# EpaperTeensyBoard.net
KiCad netlist of a schematic drawn in EAGLE
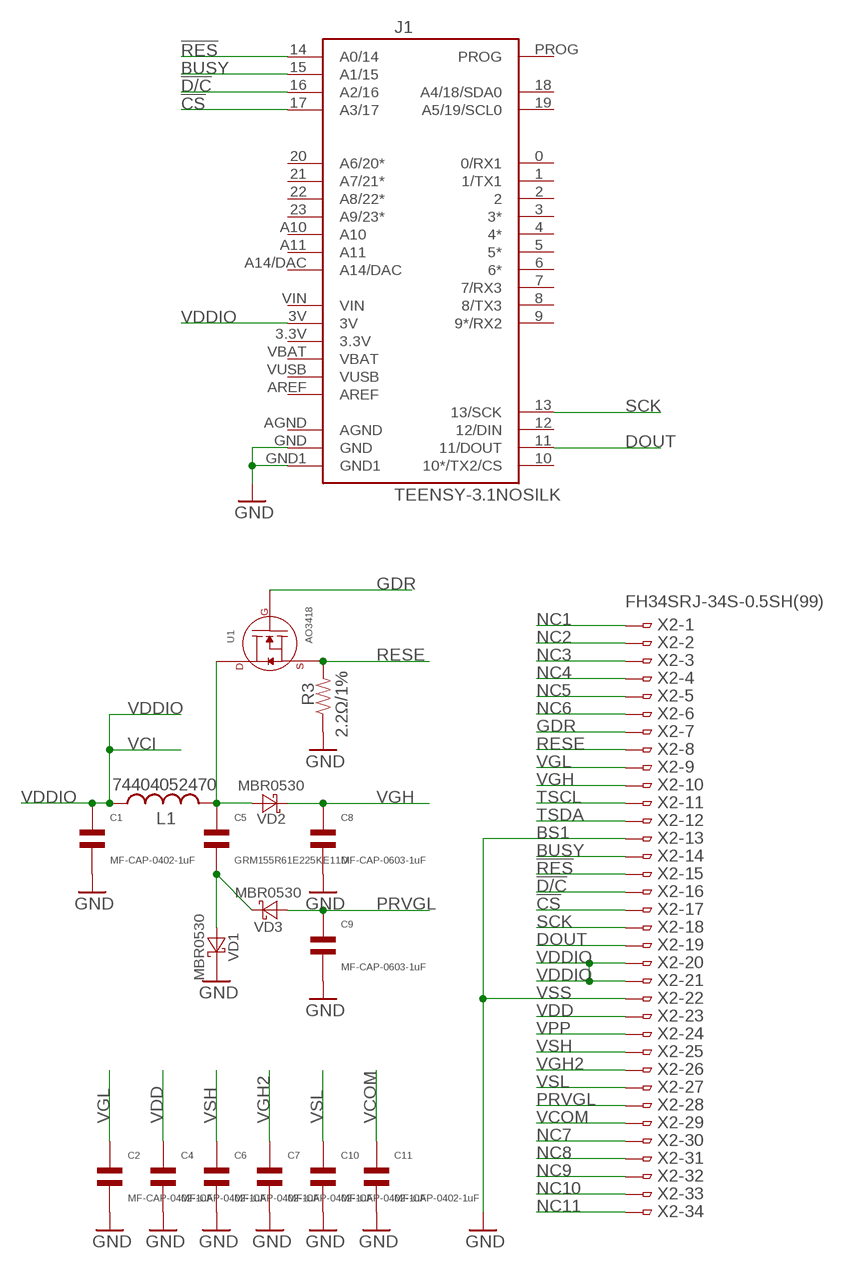
[diagram p0: schematic, sheet 1]

(export (version "E")
  (design (tool "Eeschema 10.0.6"))
  (components
    (comp (ref "C1")
      (value "MF-CAP-0402-1uF")
      (footprint "eagle-import:C0805")
      (libsource (lib "eagle-import") (part "CAPACITOR_NP_0805"))
    )
    (comp (ref "C2")
      (value "MF-CAP-0402-1uF")
      (footprint "eagle-import:C0805")
      (libsource (lib "eagle-import") (part "CAPACITOR_NP_0805"))
    )
    (comp (ref "C4")
      (value "MF-CAP-0402-1uF")
      (footprint "eagle-import:C0805")
      (libsource (lib "eagle-import") (part "CAPACITOR_NP_0805"))
    )
    (comp (ref "C5")
      (value "GRM155R61E225KE11D")
      (footprint "eagle-import:C0805")
      (libsource (lib "eagle-import") (part "CAPACITOR_NP_0805"))
    )
    (comp (ref "C6")
      (value "MF-CAP-0402-1uF")
      (footprint "eagle-import:C0805")
      (libsource (lib "eagle-import") (part "CAPACITOR_NP_0805"))
    )
    (comp (ref "C7")
      (value "MF-CAP-0402-1uF")
      (footprint "eagle-import:C0805")
      (libsource (lib "eagle-import") (part "CAPACITOR_NP_0805"))
    )
    (comp (ref "C8")
      (value "MF-CAP-0603-1uF")
      (footprint "eagle-import:C0805")
      (libsource (lib "eagle-import") (part "CAPACITOR_NP_0805"))
    )
    (comp (ref "C9")
      (value "MF-CAP-0603-1uF")
      (footprint "eagle-import:C0805")
      (libsource (lib "eagle-import") (part "CAPACITOR_NP_0805"))
    )
    (comp (ref "C10")
      (value "MF-CAP-0402-1uF")
      (footprint "eagle-import:C0805")
      (libsource (lib "eagle-import") (part "CAPACITOR_NP_0805"))
    )
    (comp (ref "C11")
      (value "MF-CAP-0402-1uF")
      (footprint "eagle-import:C0805")
      (libsource (lib "eagle-import") (part "CAPACITOR_NP_0805"))
    )
    (comp (ref "J1")
      (value "TEENSY-3.1NOSILK")
      (footprint "eagle-import:TEENSY-3.1_NOSILK")
      (libsource (lib "eagle-import") (part "TEENSY-3.1NOSILK"))
    )
    (comp (ref "L1")
      (value "74404052470")
      (footprint "eagle-import:POWER-CHOKE_WE-TPC")
      (libsource (lib "eagle-import") (part "L-USWE-TPC"))
    )
    (comp (ref "R3")
      (value "2.2Ω/1%")
      (footprint "eagle-import:R0805")
      (libsource (lib "eagle-import") (part "RESISTOR_0805"))
    )
    (comp (ref "U1")
      (value "AO3418")
      (footprint "eagle-import:SOT-23-3")
      (libsource (lib "eagle-import") (part "N-CHANNEL_FET_SOT-23-3"))
    )
    (comp (ref "VD1")
      (value "MBR0530")
      (footprint "eagle-import:SOD123")
      (libsource (lib "eagle-import") (part "DIODE-SCHOTTKY-SOD123"))
    )
    (comp (ref "VD2")
      (value "MBR0530")
      (footprint "eagle-import:SOD123")
      (libsource (lib "eagle-import") (part "DIODE-SCHOTTKY-SOD123"))
    )
    (comp (ref "VD3")
      (value "MBR0530")
      (footprint "eagle-import:SOD123")
      (libsource (lib "eagle-import") (part "DIODE-SCHOTTKY-SOD123"))
    )
    (comp (ref "X2")
      (value "FH34SRJ-34S-0.5SH(99)")
      (footprint "eagle-import:FH12-34S-0.5SH")
      (libsource (lib "eagle-import") (part "FH12-34S-0.5SH"))
    )
  )
  (nets
    (net (code "1") (name "/BUSY") (class "Default")
      (node (ref "J1") (pin "15") (pinfunction "A1/15_15") (pintype "bidirectional"))
      (node (ref "X2") (pin "14") (pinfunction "1_14") (pintype "passive"))
    )
    (net (code "2") (name "/DOUT") (class "Default")
      (node (ref "J1") (pin "11") (pinfunction "11/DOUT_11") (pintype "bidirectional"))
      (node (ref "X2") (pin "19") (pinfunction "1_19") (pintype "passive"))
    )
    (net (code "3") (name "/GDR") (class "Default")
      (node (ref "U1") (pin "P$1") (pinfunction "GATE_P$1") (pintype "bidirectional"))
      (node (ref "X2") (pin "7") (pinfunction "1_7") (pintype "passive"))
    )
    (net (code "4") (name "/NC1") (class "Default")
      (node (ref "X2") (pin "1") (pinfunction "1_1") (pintype "passive"))
    )
    (net (code "5") (name "/NC2") (class "Default")
      (node (ref "X2") (pin "2") (pinfunction "1_2") (pintype "passive"))
    )
    (net (code "6") (name "/NC3") (class "Default")
      (node (ref "X2") (pin "3") (pinfunction "1_3") (pintype "passive"))
    )
    (net (code "7") (name "/NC4") (class "Default")
      (node (ref "X2") (pin "4") (pinfunction "1_4") (pintype "passive"))
    )
    (net (code "8") (name "/NC5") (class "Default")
      (node (ref "X2") (pin "5") (pinfunction "1_5") (pintype "passive"))
    )
    (net (code "9") (name "/NC6") (class "Default")
      (node (ref "X2") (pin "6") (pinfunction "1_6") (pintype "passive"))
    )
    (net (code "10") (name "/NC7") (class "Default")
      (node (ref "X2") (pin "30") (pinfunction "1_30") (pintype "passive"))
    )
    (net (code "11") (name "/NC8") (class "Default")
      (node (ref "X2") (pin "31") (pinfunction "1_31") (pintype "passive"))
    )
    (net (code "12") (name "/NC9") (class "Default")
      (node (ref "X2") (pin "32") (pinfunction "1_32") (pintype "passive"))
    )
    (net (code "13") (name "/NC10") (class "Default")
      (node (ref "X2") (pin "33") (pinfunction "1_33") (pintype "passive"))
    )
    (net (code "14") (name "/NC11") (class "Default")
      (node (ref "X2") (pin "34") (pinfunction "1_34") (pintype "passive"))
    )
    (net (code "15") (name "/PRVGL") (class "Default")
      (node (ref "C9") (pin "P$1") (pinfunction "P$1_P$1") (pintype "passive"))
      (node (ref "VD3") (pin "A") (pinfunction "A_A") (pintype "passive"))
      (node (ref "X2") (pin "28") (pinfunction "1_28") (pintype "passive"))
    )
    (net (code "16") (name "/RESE") (class "Default")
      (node (ref "R3") (pin "P$2") (pinfunction "P$2_P$2") (pintype "passive"))
      (node (ref "U1") (pin "P$2") (pinfunction "SOURCE_P$2") (pintype "bidirectional"))
      (node (ref "X2") (pin "8") (pinfunction "1_8") (pintype "passive"))
    )
    (net (code "17") (name "/SCK") (class "Default")
      (node (ref "J1") (pin "13") (pinfunction "13/SCK_13") (pintype "bidirectional"))
      (node (ref "X2") (pin "18") (pinfunction "1_18") (pintype "passive"))
    )
    (net (code "18") (name "/TSCL") (class "Default")
      (node (ref "X2") (pin "11") (pinfunction "1_11") (pintype "passive"))
    )
    (net (code "19") (name "/TSDA") (class "Default")
      (node (ref "X2") (pin "12") (pinfunction "1_12") (pintype "passive"))
    )
    (net (code "20") (name "/VCOM") (class "Default")
      (node (ref "C11") (pin "P$1") (pinfunction "P$1_P$1") (pintype "passive"))
      (node (ref "X2") (pin "29") (pinfunction "1_29") (pintype "passive"))
    )
    (net (code "21") (name "/VDD") (class "Default")
      (node (ref "C4") (pin "P$1") (pinfunction "P$1_P$1") (pintype "passive"))
      (node (ref "X2") (pin "23") (pinfunction "1_23") (pintype "passive"))
    )
    (net (code "22") (name "/VDDIO") (class "Default")
      (node (ref "C1") (pin "P$1") (pinfunction "P$1_P$1") (pintype "passive"))
      (node (ref "J1") (pin "3V") (pinfunction "3V_3V") (pintype "bidirectional"))
      (node (ref "L1") (pin "1") (pinfunction "1_1") (pintype "passive"))
      (node (ref "X2") (pin "20") (pinfunction "1_20") (pintype "passive"))
      (node (ref "X2") (pin "21") (pinfunction "1_21") (pintype "passive"))
    )
    (net (code "23") (name "/VGH") (class "Default")
      (node (ref "C8") (pin "P$1") (pinfunction "P$1_P$1") (pintype "passive"))
      (node (ref "VD2") (pin "C") (pinfunction "C_C") (pintype "passive"))
      (node (ref "X2") (pin "10") (pinfunction "1_10") (pintype "passive"))
    )
    (net (code "24") (name "/VGH2") (class "Default")
      (node (ref "C7") (pin "P$1") (pinfunction "P$1_P$1") (pintype "passive"))
      (node (ref "X2") (pin "26") (pinfunction "1_26") (pintype "passive"))
    )
    (net (code "25") (name "/VGL") (class "Default")
      (node (ref "C2") (pin "P$1") (pinfunction "P$1_P$1") (pintype "passive"))
      (node (ref "X2") (pin "9") (pinfunction "1_9") (pintype "passive"))
    )
    (net (code "26") (name "/VPP") (class "Default")
      (node (ref "X2") (pin "24") (pinfunction "1_24") (pintype "passive"))
    )
    (net (code "27") (name "/VSH") (class "Default")
      (node (ref "C6") (pin "P$1") (pinfunction "P$1_P$1") (pintype "passive"))
      (node (ref "X2") (pin "25") (pinfunction "1_25") (pintype "passive"))
    )
    (net (code "28") (name "/VSL") (class "Default")
      (node (ref "C10") (pin "P$1") (pinfunction "P$1_P$1") (pintype "passive"))
      (node (ref "X2") (pin "27") (pinfunction "1_27") (pintype "passive"))
    )
    (net (code "29") (name "/~{CS}") (class "Default")
      (node (ref "J1") (pin "17") (pinfunction "A3/17_17") (pintype "bidirectional"))
      (node (ref "X2") (pin "17") (pinfunction "1_17") (pintype "passive"))
    )
    (net (code "30") (name "/~{D{slash}C}") (class "Default")
      (node (ref "J1") (pin "16") (pinfunction "A2/16_16") (pintype "bidirectional"))
      (node (ref "X2") (pin "16") (pinfunction "1_16") (pintype "passive"))
    )
    (net (code "31") (name "/~{RES}") (class "Default")
      (node (ref "J1") (pin "14") (pinfunction "A0/14_14") (pintype "bidirectional"))
      (node (ref "X2") (pin "15") (pinfunction "1_15") (pintype "passive"))
    )
    (net (code "32") (name "GND") (class "Default")
      (node (ref "C1") (pin "P$2") (pinfunction "P$2_P$2") (pintype "passive"))
      (node (ref "C10") (pin "P$2") (pinfunction "P$2_P$2") (pintype "passive"))
      (node (ref "C11") (pin "P$2") (pinfunction "P$2_P$2") (pintype "passive"))
      (node (ref "C2") (pin "P$2") (pinfunction "P$2_P$2") (pintype "passive"))
      (node (ref "C4") (pin "P$2") (pinfunction "P$2_P$2") (pintype "passive"))
      (node (ref "C6") (pin "P$2") (pinfunction "P$2_P$2") (pintype "passive"))
      (node (ref "C7") (pin "P$2") (pinfunction "P$2_P$2") (pintype "passive"))
      (node (ref "C8") (pin "P$2") (pinfunction "P$2_P$2") (pintype "passive"))
      (node (ref "C9") (pin "P$2") (pinfunction "P$2_P$2") (pintype "passive"))
      (node (ref "J1") (pin "GND") (pinfunction "GND_GND") (pintype "bidirectional"))
      (node (ref "J1") (pin "GND1") (pinfunction "GND1_GND1") (pintype "bidirectional"))
      (node (ref "R3") (pin "P$1") (pinfunction "P$1_P$1") (pintype "passive"))
      (node (ref "VD1") (pin "C") (pinfunction "C_C") (pintype "passive"))
      (node (ref "X2") (pin "13") (pinfunction "1_13") (pintype "passive"))
      (node (ref "X2") (pin "22") (pinfunction "1_22") (pintype "passive"))
    )
    (net (code "33") (name "Net-(C5-PadP$2)") (class "Default")
      (node (ref "C5") (pin "P$2") (pinfunction "P$2_P$2") (pintype "passive"))
      (node (ref "VD1") (pin "A") (pinfunction "A_A") (pintype "passive"))
      (node (ref "VD3") (pin "C") (pinfunction "C_C") (pintype "passive"))
    )
    (net (code "34") (name "Net-(U1-DRAIN)") (class "Default")
      (node (ref "C5") (pin "P$1") (pinfunction "P$1_P$1") (pintype "passive"))
      (node (ref "L1") (pin "2") (pinfunction "2_2") (pintype "passive"))
      (node (ref "U1") (pin "P$3") (pinfunction "DRAIN_P$3") (pintype "bidirectional"))
      (node (ref "VD2") (pin "A") (pinfunction "A_A") (pintype "passive"))
    )
    (net (code "35") (name "unconnected-(J1-0{slash}RX1-Pad0)") (class "Default")
      (node (ref "J1") (pin "0") (pinfunction "0/RX1_0") (pintype "bidirectional"))
    )
    (net (code "36") (name "unconnected-(J1-1{slash}TX1-Pad1)") (class "Default")
      (node (ref "J1") (pin "1") (pinfunction "1/TX1_1") (pintype "bidirectional"))
    )
    (net (code "37") (name "unconnected-(J1-3*-Pad3)") (class "Default")
      (node (ref "J1") (pin "3") (pinfunction "3*_3") (pintype "bidirectional"))
    )
    (net (code "38") (name "unconnected-(J1-4*-Pad4)") (class "Default")
      (node (ref "J1") (pin "4") (pinfunction "4*_4") (pintype "bidirectional"))
    )
    (net (code "39") (name "unconnected-(J1-5*-Pad5)") (class "Default")
      (node (ref "J1") (pin "5") (pinfunction "5*_5") (pintype "bidirectional"))
    )
    (net (code "40") (name "unconnected-(J1-6*-Pad6)") (class "Default")
      (node (ref "J1") (pin "6") (pinfunction "6*_6") (pintype "bidirectional"))
    )
    (net (code "41") (name "unconnected-(J1-7{slash}RX3-Pad7)") (class "Default")
      (node (ref "J1") (pin "7") (pinfunction "7/RX3_7") (pintype "bidirectional"))
    )
    (net (code "42") (name "unconnected-(J1-8{slash}TX3-Pad8)") (class "Default")
      (node (ref "J1") (pin "8") (pinfunction "8/TX3_8") (pintype "bidirectional"))
    )
    (net (code "43") (name "unconnected-(J1-9*{slash}RX2-Pad9)") (class "Default")
      (node (ref "J1") (pin "9") (pinfunction "9*/RX2_9") (pintype "bidirectional"))
    )
    (net (code "44") (name "unconnected-(J1-10*{slash}TX2{slash}CS-Pad10)") (class "Default")
      (node (ref "J1") (pin "10") (pinfunction "10*/TX2/CS_10") (pintype "bidirectional"))
    )
    (net (code "45") (name "unconnected-(J1-12{slash}DIN-Pad12)") (class "Default")
      (node (ref "J1") (pin "12") (pinfunction "12/DIN_12") (pintype "bidirectional"))
    )
    (net (code "46") (name "unconnected-(J1-A4{slash}18{slash}SDA0-Pad18)") (class "Default")
      (node (ref "J1") (pin "18") (pinfunction "A4/18/SDA0_18") (pintype "bidirectional"))
    )
    (net (code "47") (name "unconnected-(J1-A5{slash}19{slash}SCL0-Pad19)") (class "Default")
      (node (ref "J1") (pin "19") (pinfunction "A5/19/SCL0_19") (pintype "bidirectional"))
    )
    (net (code "48") (name "unconnected-(J1-A6{slash}20*-Pad20)") (class "Default")
      (node (ref "J1") (pin "20") (pinfunction "A6/20*_20") (pintype "bidirectional"))
    )
    (net (code "49") (name "unconnected-(J1-A7{slash}21*-Pad21)") (class "Default")
      (node (ref "J1") (pin "21") (pinfunction "A7/21*_21") (pintype "bidirectional"))
    )
    (net (code "50") (name "unconnected-(J1-A8{slash}22*-Pad22)") (class "Default")
      (node (ref "J1") (pin "22") (pinfunction "A8/22*_22") (pintype "bidirectional"))
    )
    (net (code "51") (name "unconnected-(J1-A9{slash}23*-Pad23)") (class "Default")
      (node (ref "J1") (pin "23") (pinfunction "A9/23*_23") (pintype "bidirectional"))
    )
    (net (code "52") (name "unconnected-(J1-Pad2)") (class "Default")
      (node (ref "J1") (pin "2") (pinfunction "2_2") (pintype "bidirectional"))
    )
    (net (code "53") (name "unconnected-(J1-Pad3.3V)") (class "Default")
      (node (ref "J1") (pin "3.3V") (pinfunction "3.3V_3.3V") (pintype "bidirectional"))
    )
    (net (code "54") (name "unconnected-(J1-PadA10)") (class "Default")
      (node (ref "J1") (pin "A10") (pinfunction "A10_A10") (pintype "bidirectional"))
    )
    (net (code "55") (name "unconnected-(J1-PadA11)") (class "Default")
      (node (ref "J1") (pin "A11") (pinfunction "A11_A11") (pintype "bidirectional"))
    )
    (net (code "56") (name "unconnected-(J1-PadA14{slash}DAC)") (class "Default")
      (node (ref "J1") (pin "A14/DAC") (pinfunction "A14/DAC_A14/DAC") (pintype "bidirectional"))
    )
    (net (code "57") (name "unconnected-(J1-PadAGND)") (class "Default")
      (node (ref "J1") (pin "AGND") (pinfunction "AGND_AGND") (pintype "bidirectional"))
    )
    (net (code "58") (name "unconnected-(J1-PadAREF)") (class "Default")
      (node (ref "J1") (pin "AREF") (pinfunction "AREF_AREF") (pintype "bidirectional"))
    )
    (net (code "59") (name "unconnected-(J1-PadPROG)") (class "Default")
      (node (ref "J1") (pin "PROG") (pinfunction "PROG_PROG") (pintype "bidirectional"))
    )
    (net (code "60") (name "unconnected-(J1-PadVBAT)") (class "Default")
      (node (ref "J1") (pin "VBAT") (pinfunction "VBAT_VBAT") (pintype "bidirectional"))
    )
    (net (code "61") (name "unconnected-(J1-PadVIN)") (class "Default")
      (node (ref "J1") (pin "VIN") (pinfunction "VIN_VIN") (pintype "bidirectional"))
    )
    (net (code "62") (name "unconnected-(J1-PadVUSB)") (class "Default")
      (node (ref "J1") (pin "VUSB") (pinfunction "VUSB_VUSB") (pintype "bidirectional"))
    )
  )
)
